# 000_Block_Diagram.net
KiCad netlist of a schematic drawn in Altium Designer
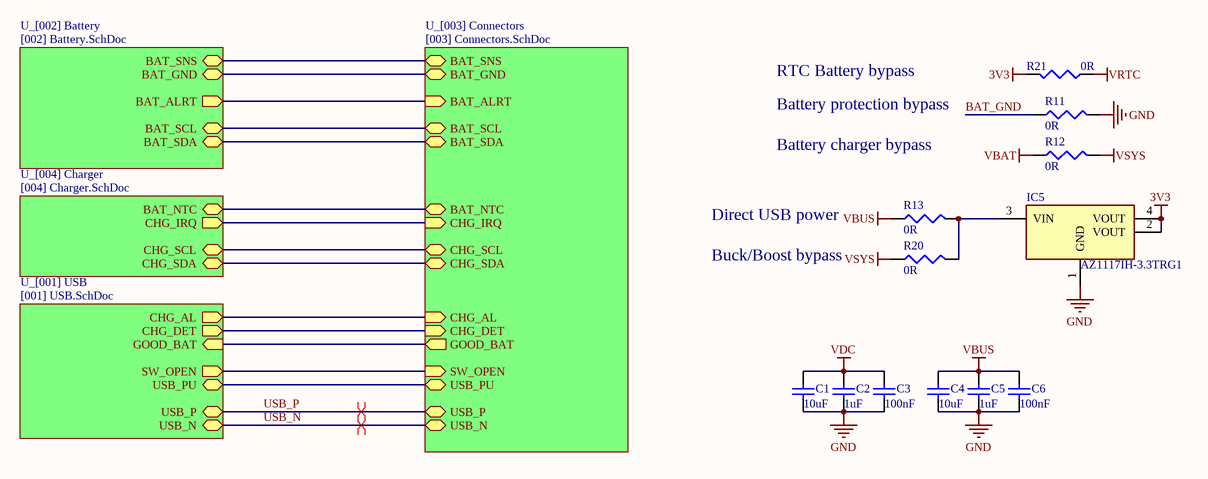
[diagram p0: [000] Block Diagram.SchDoc]

(export (version "E")
  (design (tool "Eeschema 10.0.6"))
  (components
    (comp (ref "C1")
      (value "10uF")
      (footprint "1608[0603]")
      (description "Capacitor (Semiconductor SIM Model)")
      (fields (field (name "Comment") "Cap Semi") (field (name "PUBLISHER") "Altium Limited"))
      (libsource (lib "Miscellaneous Devices") (part "Cap Semi"))
    )
    (comp (ref "C2")
      (value "1uF")
      (footprint "1608[0603]")
      (description "Capacitor (Semiconductor SIM Model)")
      (fields (field (name "Comment") "Cap Semi") (field (name "PUBLISHER") "Altium Limited"))
      (libsource (lib "Miscellaneous Devices") (part "Cap Semi"))
    )
    (comp (ref "C3")
      (value "100nF")
      (footprint "1608[0603]")
      (description "Capacitor (Semiconductor SIM Model)")
      (fields (field (name "Comment") "Cap Semi") (field (name "PUBLISHER") "Altium Limited"))
      (libsource (lib "Miscellaneous Devices") (part "Cap Semi"))
    )
    (comp (ref "C4")
      (value "10uF")
      (footprint "1608[0603]")
      (description "Capacitor (Semiconductor SIM Model)")
      (fields (field (name "Comment") "Cap Semi") (field (name "PUBLISHER") "Altium Limited"))
      (libsource (lib "Miscellaneous Devices") (part "Cap Semi"))
    )
    (comp (ref "C5")
      (value "1uF")
      (footprint "1608[0603]")
      (description "Capacitor (Semiconductor SIM Model)")
      (fields (field (name "Comment") "Cap Semi") (field (name "PUBLISHER") "Altium Limited"))
      (libsource (lib "Miscellaneous Devices") (part "Cap Semi"))
    )
    (comp (ref "C6")
      (value "100nF")
      (footprint "1608[0603]")
      (description "Capacitor (Semiconductor SIM Model)")
      (fields (field (name "Comment") "Cap Semi") (field (name "PUBLISHER") "Altium Limited"))
      (libsource (lib "Miscellaneous Devices") (part "Cap Semi"))
    )
    (comp (ref "IC5")
      (value "AZ1117IH-3.3TRG1")
      (footprint "SamacSys:SOT230P700X170-4N")
      (description "Integrated Circuit")
      (fields (field (name "MOUSER2 PART NUMBER") "621-AZ1117IH-3.3TRG1"))
      (libsource (lib "SamacSys") (part "AZ1117IH-3.3TRG1"))
    )
    (comp (ref "R11")
      (value "0R")
      (footprint "J1-0603")
      (description "Resistor")
      (fields (field (name "Comment") "Res3") (field (name "PUBLISHER") "Altium Limited"))
      (libsource (lib "Miscellaneous Devices") (part "Res3"))
    )
    (comp (ref "R12")
      (value "0R")
      (footprint "J1-0603")
      (description "Resistor")
      (fields (field (name "Comment") "Res3") (field (name "PUBLISHER") "Altium Limited"))
      (libsource (lib "Miscellaneous Devices") (part "Res3"))
    )
    (comp (ref "R13")
      (value "0R")
      (footprint "J1-0603")
      (description "Resistor")
      (fields (field (name "Comment") "Res3") (field (name "PUBLISHER") "Altium Limited"))
      (libsource (lib "Miscellaneous Devices") (part "Res3"))
    )
    (comp (ref "R20")
      (value "0R")
      (footprint "J1-0603")
      (description "Resistor")
      (fields (field (name "Comment") "Res3") (field (name "PUBLISHER") "Altium Limited"))
      (libsource (lib "Miscellaneous Devices") (part "Res3"))
    )
    (comp (ref "R21")
      (value "0R")
      (footprint "J1-0603")
      (description "Resistor")
      (fields (field (name "Comment") "Res3") (field (name "PUBLISHER") "Altium Limited"))
      (libsource (lib "Miscellaneous Devices") (part "Res3"))
    )
  )
  (nets
    (net (code "2") (name "/BAT_GND") (class "Default")
      (node (ref "R11") (pin "1") (pinfunction "1_1") (pintype "passive"))
    )
    (net (code "18") (name "3V3") (class "Default")
      (node (ref "IC5") (pin "2") (pinfunction "VOUT_2") (pintype "passive"))
      (node (ref "IC5") (pin "4") (pinfunction "VOUT_4") (pintype "passive"))
      (node (ref "R21") (pin "2") (pinfunction "2_2") (pintype "passive"))
    )
    (net (code "19") (name "GND") (class "Default")
      (node (ref "C1") (pin "1") (pinfunction "1_1") (pintype "passive"))
      (node (ref "C2") (pin "1") (pinfunction "1_1") (pintype "passive"))
      (node (ref "C3") (pin "1") (pinfunction "1_1") (pintype "passive"))
      (node (ref "C4") (pin "1") (pinfunction "1_1") (pintype "passive"))
      (node (ref "C5") (pin "1") (pinfunction "1_1") (pintype "passive"))
      (node (ref "C6") (pin "1") (pinfunction "1_1") (pintype "passive"))
      (node (ref "IC5") (pin "1") (pinfunction "GND_1") (pintype "passive"))
      (node (ref "R11") (pin "2") (pinfunction "2_2") (pintype "passive"))
    )
    (net (code "20") (name "Net-(IC5-VIN)") (class "Default")
      (node (ref "IC5") (pin "3") (pinfunction "VIN_3") (pintype "passive"))
      (node (ref "R13") (pin "2") (pinfunction "2_2") (pintype "passive"))
      (node (ref "R20") (pin "2") (pinfunction "2_2") (pintype "passive"))
    )
    (net (code "21") (name "VBAT") (class "Default")
      (node (ref "R12") (pin "1") (pinfunction "1_1") (pintype "passive"))
    )
    (net (code "22") (name "VBUS") (class "Default")
      (node (ref "C4") (pin "2") (pinfunction "2_2") (pintype "passive"))
      (node (ref "C5") (pin "2") (pinfunction "2_2") (pintype "passive"))
      (node (ref "C6") (pin "2") (pinfunction "2_2") (pintype "passive"))
      (node (ref "R13") (pin "1") (pinfunction "1_1") (pintype "passive"))
    )
    (net (code "23") (name "VDC") (class "Default")
      (node (ref "C1") (pin "2") (pinfunction "2_2") (pintype "passive"))
      (node (ref "C2") (pin "2") (pinfunction "2_2") (pintype "passive"))
      (node (ref "C3") (pin "2") (pinfunction "2_2") (pintype "passive"))
    )
    (net (code "24") (name "VRTC") (class "Default")
      (node (ref "R21") (pin "1") (pinfunction "1_1") (pintype "passive"))
    )
    (net (code "25") (name "VSYS") (class "Default")
      (node (ref "R12") (pin "2") (pinfunction "2_2") (pintype "passive"))
      (node (ref "R20") (pin "1") (pinfunction "1_1") (pintype "passive"))
    )
  )
)
